# design.net
KiCad netlist of a schematic drawn in Altium Designer
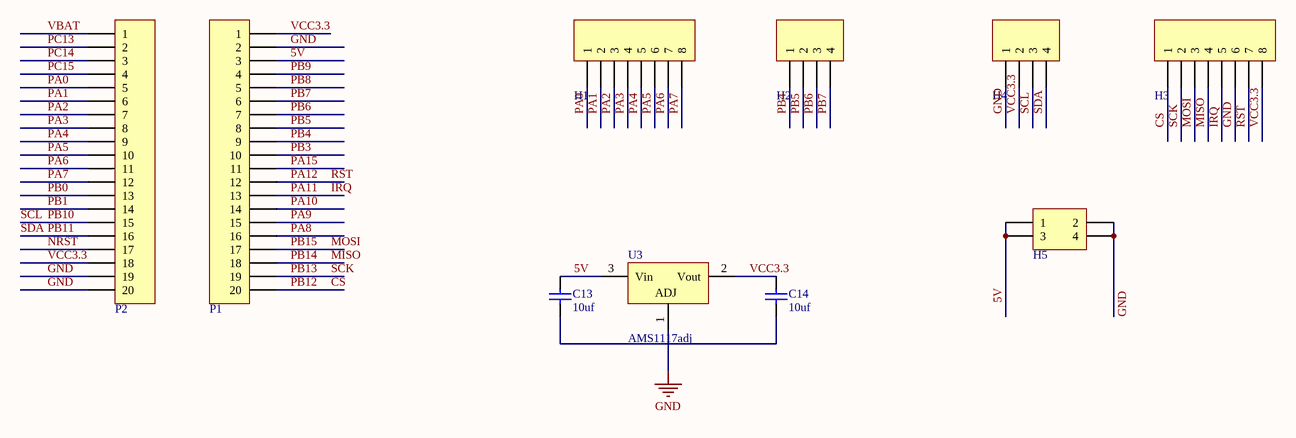
[diagram p0: 底座.SchDoc]

(export (version "E")
  (design (tool "Eeschema 10.0.6"))
  (components
    (comp (ref "C13")
      (value "~")
      (footprint "0603C")
      (description "0603瓷片电容")
      (fields (field (name "ALTIUM_UNNAMED_1") "10uf"))
      (libsource (lib "0.电阻电容电感") (part "Cap_0603"))
    )
    (comp (ref "C14")
      (value "~")
      (footprint "0603C")
      (description "0603瓷片电容")
      (fields (field (name "ALTIUM_UNNAMED_1") "10uf"))
      (libsource (lib "0.电阻电容电感") (part "Cap_0603"))
    )
    (comp (ref "H1")
      (value "Header 8")
      (footprint "HDR1X8")
      (description "Header, 8-Pin")
      (fields (field (name "PUBLISHER") "Altium Limited"))
      (libsource (lib "9.接插件 连接器") (part "Header 8"))
    )
    (comp (ref "H2")
      (value "Header 4")
      (footprint "HDR1X4")
      (description "Header, 4-Pin")
      (fields (field (name "PUBLISHER") "Altium Limited"))
      (libsource (lib "9.接插件 连接器") (part "Header 4"))
    )
    (comp (ref "H3")
      (value "Header 8")
      (footprint "HDR1X8")
      (description "Header, 8-Pin")
      (fields (field (name "PUBLISHER") "Altium Limited"))
      (libsource (lib "9.接插件 连接器") (part "Header 8"))
    )
    (comp (ref "H4")
      (value "Header 4")
      (footprint "HDR1X4")
      (description "Header, 4-Pin")
      (fields (field (name "PUBLISHER") "Altium Limited"))
      (libsource (lib "9.接插件 连接器") (part "Header 4"))
    )
    (comp (ref "H5")
      (value "Header 2X2")
      (footprint "HDR2X2")
      (description "Header, 2-Pin, Dual row")
      (fields (field (name "PUBLISHER") "Altium Limited"))
      (libsource (lib "9.接插件 连接器") (part "Header 2X2"))
    )
    (comp (ref "P1")
      (value "Header 20")
      (footprint "HDR1X20")
      (description "Header, 20-Pin")
      (fields (field (name "PUBLISHER") "Altium Limited"))
      (libsource (lib "9.接插件 连接器") (part "Header 20"))
    )
    (comp (ref "P2")
      (value "Header 20")
      (footprint "HDR1X20")
      (description "Header, 20-Pin")
      (fields (field (name "PUBLISHER") "Altium Limited"))
      (libsource (lib "") (part "Header 20_1"))
    )
    (comp (ref "U3")
      (value "AMS1117adj")
      (footprint "SOT223")
      (description "三端稳压芯片可调输出")
      (libsource (lib "5.电源器件") (part "AMS1117adj"))
    )
  )
  (nets
    (net (code "1") (name "/5V") (class "Default")
      (node (ref "C13") (pin "1") (pinfunction "1_1") (pintype "passive"))
      (node (ref "H5") (pin "1") (pinfunction "1_1") (pintype "passive"))
      (node (ref "H5") (pin "3") (pinfunction "3_3") (pintype "passive"))
      (node (ref "P1") (pin "3") (pinfunction "3_3") (pintype "passive"))
      (node (ref "U3") (pin "3") (pinfunction "Vin_3") (pintype "passive"))
    )
    (net (code "2") (name "/CS") (class "Default")
      (node (ref "H3") (pin "1") (pinfunction "1_1") (pintype "passive"))
      (node (ref "P1") (pin "20") (pinfunction "20_20") (pintype "passive"))
    )
    (net (code "3") (name "/IRQ") (class "Default")
      (node (ref "H3") (pin "5") (pinfunction "5_5") (pintype "passive"))
      (node (ref "P1") (pin "13") (pinfunction "13_13") (pintype "passive"))
    )
    (net (code "4") (name "/MISO") (class "Default")
      (node (ref "H3") (pin "4") (pinfunction "4_4") (pintype "passive"))
      (node (ref "P1") (pin "18") (pinfunction "18_18") (pintype "passive"))
    )
    (net (code "5") (name "/MOSI") (class "Default")
      (node (ref "H3") (pin "3") (pinfunction "3_3") (pintype "passive"))
      (node (ref "P1") (pin "17") (pinfunction "17_17") (pintype "passive"))
    )
    (net (code "6") (name "/NRST") (class "Default")
      (node (ref "P2") (pin "17") (pinfunction "17_17") (pintype "passive"))
    )
    (net (code "7") (name "/PA0") (class "Default")
      (node (ref "H1") (pin "1") (pinfunction "1_1") (pintype "passive"))
      (node (ref "P2") (pin "5") (pinfunction "5_5") (pintype "passive"))
    )
    (net (code "8") (name "/PA1") (class "Default")
      (node (ref "H1") (pin "2") (pinfunction "2_2") (pintype "passive"))
      (node (ref "P2") (pin "6") (pinfunction "6_6") (pintype "passive"))
    )
    (net (code "9") (name "/PA2") (class "Default")
      (node (ref "H1") (pin "3") (pinfunction "3_3") (pintype "passive"))
      (node (ref "P2") (pin "7") (pinfunction "7_7") (pintype "passive"))
    )
    (net (code "10") (name "/PA3") (class "Default")
      (node (ref "H1") (pin "4") (pinfunction "4_4") (pintype "passive"))
      (node (ref "P2") (pin "8") (pinfunction "8_8") (pintype "passive"))
    )
    (net (code "11") (name "/PA4") (class "Default")
      (node (ref "H1") (pin "5") (pinfunction "5_5") (pintype "passive"))
      (node (ref "P2") (pin "9") (pinfunction "9_9") (pintype "passive"))
    )
    (net (code "12") (name "/PA5") (class "Default")
      (node (ref "H1") (pin "6") (pinfunction "6_6") (pintype "passive"))
      (node (ref "P2") (pin "10") (pinfunction "10_10") (pintype "passive"))
    )
    (net (code "13") (name "/PA6") (class "Default")
      (node (ref "H1") (pin "7") (pinfunction "7_7") (pintype "passive"))
      (node (ref "P2") (pin "11") (pinfunction "11_11") (pintype "passive"))
    )
    (net (code "14") (name "/PA7") (class "Default")
      (node (ref "H1") (pin "8") (pinfunction "8_8") (pintype "passive"))
      (node (ref "P2") (pin "12") (pinfunction "12_12") (pintype "passive"))
    )
    (net (code "15") (name "/PA8") (class "Default")
      (node (ref "P1") (pin "16") (pinfunction "16_16") (pintype "passive"))
    )
    (net (code "16") (name "/PA9") (class "Default")
      (node (ref "P1") (pin "15") (pinfunction "15_15") (pintype "passive"))
    )
    (net (code "17") (name "/PA10") (class "Default")
      (node (ref "P1") (pin "14") (pinfunction "14_14") (pintype "passive"))
    )
    (net (code "18") (name "/PA12") (class "Default")
      (node (ref "H3") (pin "7") (pinfunction "7_7") (pintype "passive"))
      (node (ref "P1") (pin "12") (pinfunction "12_12") (pintype "passive"))
    )
    (net (code "19") (name "/PA15") (class "Default")
      (node (ref "P1") (pin "11") (pinfunction "11_11") (pintype "passive"))
    )
    (net (code "20") (name "/PB0") (class "Default")
      (node (ref "P2") (pin "13") (pinfunction "13_13") (pintype "passive"))
    )
    (net (code "21") (name "/PB1") (class "Default")
      (node (ref "P2") (pin "14") (pinfunction "14_14") (pintype "passive"))
    )
    (net (code "22") (name "/PB3") (class "Default")
      (node (ref "P1") (pin "10") (pinfunction "10_10") (pintype "passive"))
    )
    (net (code "23") (name "/PB4") (class "Default")
      (node (ref "H2") (pin "1") (pinfunction "1_1") (pintype "passive"))
      (node (ref "P1") (pin "9") (pinfunction "9_9") (pintype "passive"))
    )
    (net (code "24") (name "/PB5") (class "Default")
      (node (ref "H2") (pin "2") (pinfunction "2_2") (pintype "passive"))
      (node (ref "P1") (pin "8") (pinfunction "8_8") (pintype "passive"))
    )
    (net (code "25") (name "/PB6") (class "Default")
      (node (ref "H2") (pin "3") (pinfunction "3_3") (pintype "passive"))
      (node (ref "P1") (pin "7") (pinfunction "7_7") (pintype "passive"))
    )
    (net (code "26") (name "/PB7") (class "Default")
      (node (ref "H2") (pin "4") (pinfunction "4_4") (pintype "passive"))
      (node (ref "P1") (pin "6") (pinfunction "6_6") (pintype "passive"))
    )
    (net (code "27") (name "/PB8") (class "Default")
      (node (ref "P1") (pin "5") (pinfunction "5_5") (pintype "passive"))
    )
    (net (code "28") (name "/PB9") (class "Default")
      (node (ref "P1") (pin "4") (pinfunction "4_4") (pintype "passive"))
    )
    (net (code "29") (name "/PB10") (class "Default")
      (node (ref "H4") (pin "3") (pinfunction "3_3") (pintype "passive"))
      (node (ref "P2") (pin "15") (pinfunction "15_15") (pintype "passive"))
    )
    (net (code "30") (name "/PB11") (class "Default")
      (node (ref "H4") (pin "4") (pinfunction "4_4") (pintype "passive"))
      (node (ref "P2") (pin "16") (pinfunction "16_16") (pintype "passive"))
    )
    (net (code "31") (name "/PB13") (class "Default")
      (node (ref "H3") (pin "2") (pinfunction "2_2") (pintype "passive"))
      (node (ref "P1") (pin "19") (pinfunction "19_19") (pintype "passive"))
    )
    (net (code "32") (name "/PC13") (class "Default")
      (node (ref "P2") (pin "2") (pinfunction "2_2") (pintype "passive"))
    )
    (net (code "33") (name "/PC14") (class "Default")
      (node (ref "P2") (pin "3") (pinfunction "3_3") (pintype "passive"))
    )
    (net (code "34") (name "/PC15") (class "Default")
      (node (ref "P2") (pin "4") (pinfunction "4_4") (pintype "passive"))
    )
    (net (code "35") (name "/VBAT") (class "Default")
      (node (ref "P2") (pin "1") (pinfunction "1_1") (pintype "passive"))
    )
    (net (code "36") (name "/VCC3.3") (class "Default")
      (node (ref "C14") (pin "1") (pinfunction "1_1") (pintype "passive"))
      (node (ref "H3") (pin "8") (pinfunction "8_8") (pintype "passive"))
      (node (ref "H4") (pin "2") (pinfunction "2_2") (pintype "passive"))
      (node (ref "P1") (pin "1") (pinfunction "1_1") (pintype "passive"))
      (node (ref "P2") (pin "18") (pinfunction "18_18") (pintype "passive"))
      (node (ref "U3") (pin "2") (pinfunction "Vout_2") (pintype "passive"))
    )
    (net (code "37") (name "GND") (class "Default")
      (node (ref "H3") (pin "6") (pinfunction "6_6") (pintype "passive"))
      (node (ref "H4") (pin "1") (pinfunction "1_1") (pintype "passive"))
      (node (ref "H5") (pin "2") (pinfunction "2_2") (pintype "passive"))
      (node (ref "H5") (pin "4") (pinfunction "4_4") (pintype "passive"))
      (node (ref "P1") (pin "2") (pinfunction "2_2") (pintype "passive"))
      (node (ref "P2") (pin "19") (pinfunction "19_19") (pintype "passive"))
      (node (ref "P2") (pin "20") (pinfunction "20_20") (pintype "passive"))
      (node (ref "U3") (pin "1") (pinfunction "ADJ_1") (pintype "passive"))
    )
    (net (code "38") (name "Net-(C13-Pad2)") (class "Default")
      (node (ref "C13") (pin "2") (pinfunction "2_2") (pintype "passive"))
      (node (ref "C14") (pin "2") (pinfunction "2_2") (pintype "passive"))
    )
  )
)
